# Dongle.net
KiCad netlist of a schematic drawn in EAGLE
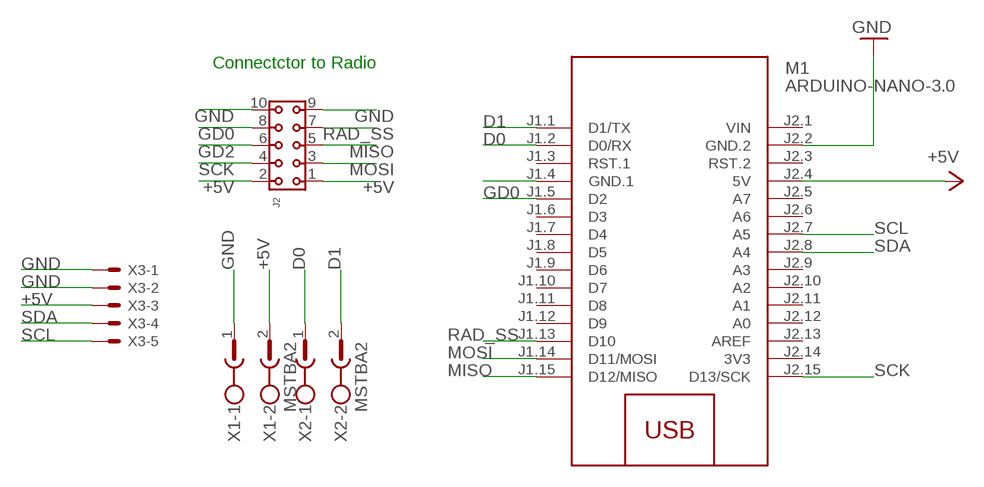
[diagram p0: schematic, sheet 1]

(export (version "E")
  (design (tool "Eeschema 10.0.6"))
  (components
    (comp (ref "J2")
      (value "6130XX21821_61301021821")
      (footprint "eagle-import:61301021821")
      (libsource (lib "eagle-import") (part "6130XX21821_61301021821"))
    )
    (comp (ref "M1")
      (value "ARDUINO-NANO-3.0")
      (footprint "eagle-import:ARDUINO-NANO-3.0")
      (libsource (lib "eagle-import") (part "ARDUINO-NANO-3.0"))
    )
    (comp (ref "X1")
      (value "MSTBA2")
      (footprint "eagle-import:MSTBA2")
      (fields (field (name "MF") "FARNELL") (field (name "MPN") "1757242"))
      (libsource (lib "eagle-import") (part "MSTBA2"))
    )
    (comp (ref "X2")
      (value "MSTBA2")
      (footprint "eagle-import:MSTBA2")
      (fields (field (name "MF") "FARNELL") (field (name "MPN") "1757242"))
      (libsource (lib "eagle-import") (part "MSTBA2"))
    )
    (comp (ref "X3")
      (value "KK-156-5")
      (footprint "eagle-import:KK-156-5")
      (fields (field (name "MF") "MOLEX"))
      (libsource (lib "eagle-import") (part "KK-156-5"))
    )
  )
  (nets
    (net (code "1") (name "+5V") (class "Default")
      (node (ref "J2") (pin "1") (pinfunction "1_1") (pintype "passive"))
      (node (ref "J2") (pin "2") (pinfunction "2_2") (pintype "passive"))
      (node (ref "M1") (pin "J2.4") (pinfunction "5V_J2.4") (pintype "power_in"))
      (node (ref "X1") (pin "2") (pinfunction "1_2") (pintype "passive"))
      (node (ref "X3") (pin "3") (pinfunction "S_3") (pintype "passive"))
    )
    (net (code "2") (name "/3V3") (class "Default")
      (node (ref "M1") (pin "J2.14") (pinfunction "3V3_J2.14") (pintype "power_in"))
    )
    (net (code "3") (name "/D0") (class "Default")
      (node (ref "M1") (pin "J1.2") (pinfunction "D0/RX_J1.2") (pintype "bidirectional"))
      (node (ref "X2") (pin "1") (pinfunction "1_1") (pintype "passive"))
    )
    (net (code "4") (name "/D1") (class "Default")
      (node (ref "M1") (pin "J1.1") (pinfunction "D1/TX_J1.1") (pintype "bidirectional"))
      (node (ref "X2") (pin "2") (pinfunction "1_2") (pintype "passive"))
    )
    (net (code "5") (name "/GD0") (class "Default")
      (node (ref "J2") (pin "8") (pinfunction "8_8") (pintype "passive"))
      (node (ref "M1") (pin "J1.5") (pinfunction "D2_J1.5") (pintype "bidirectional"))
    )
    (net (code "6") (name "/GD2") (class "Default")
      (node (ref "J2") (pin "6") (pinfunction "6_6") (pintype "passive"))
    )
    (net (code "7") (name "/MISO") (class "Default")
      (node (ref "J2") (pin "5") (pinfunction "5_5") (pintype "passive"))
      (node (ref "M1") (pin "J1.15") (pinfunction "D12/MISO_J1.15") (pintype "bidirectional"))
    )
    (net (code "8") (name "/MOSI") (class "Default")
      (node (ref "J2") (pin "3") (pinfunction "3_3") (pintype "passive"))
      (node (ref "M1") (pin "J1.14") (pinfunction "D11/MOSI_J1.14") (pintype "bidirectional"))
    )
    (net (code "9") (name "/RAD_SS") (class "Default")
      (node (ref "J2") (pin "7") (pinfunction "7_7") (pintype "passive"))
      (node (ref "M1") (pin "J1.13") (pinfunction "D10_J1.13") (pintype "bidirectional"))
    )
    (net (code "10") (name "/SCK") (class "Default")
      (node (ref "J2") (pin "4") (pinfunction "4_4") (pintype "passive"))
      (node (ref "M1") (pin "J2.15") (pinfunction "D13/SCK_J2.15") (pintype "bidirectional"))
    )
    (net (code "11") (name "/SCL") (class "Default")
      (node (ref "M1") (pin "J2.7") (pinfunction "A5_J2.7") (pintype "bidirectional"))
      (node (ref "X3") (pin "5") (pinfunction "S_5") (pintype "passive"))
    )
    (net (code "12") (name "/SDA") (class "Default")
      (node (ref "M1") (pin "J2.8") (pinfunction "A4_J2.8") (pintype "bidirectional"))
      (node (ref "X3") (pin "4") (pinfunction "S_4") (pintype "passive"))
    )
    (net (code "13") (name "/VIN") (class "Default")
      (node (ref "M1") (pin "J2.1") (pinfunction "VIN_J2.1") (pintype "power_in"))
    )
    (net (code "14") (name "GND") (class "Default")
      (node (ref "J2") (pin "10") (pinfunction "10_10") (pintype "passive"))
      (node (ref "J2") (pin "9") (pinfunction "9_9") (pintype "passive"))
      (node (ref "M1") (pin "J2.2") (pinfunction "GND.2_J2.2") (pintype "power_in"))
      (node (ref "X1") (pin "1") (pinfunction "1_1") (pintype "passive"))
      (node (ref "X3") (pin "1") (pinfunction "S_1") (pintype "passive"))
      (node (ref "X3") (pin "2") (pinfunction "S_2") (pintype "passive"))
    )
    (net (code "15") (name "unconnected-(M1-A0-PadJ2.12)") (class "Default")
      (node (ref "M1") (pin "J2.12") (pinfunction "A0_J2.12") (pintype "bidirectional"))
    )
    (net (code "16") (name "unconnected-(M1-A1-PadJ2.11)") (class "Default")
      (node (ref "M1") (pin "J2.11") (pinfunction "A1_J2.11") (pintype "bidirectional"))
    )
    (net (code "17") (name "unconnected-(M1-A2-PadJ2.10)") (class "Default")
      (node (ref "M1") (pin "J2.10") (pinfunction "A2_J2.10") (pintype "bidirectional"))
    )
    (net (code "18") (name "unconnected-(M1-A3-PadJ2.9)") (class "Default")
      (node (ref "M1") (pin "J2.9") (pinfunction "A3_J2.9") (pintype "bidirectional"))
    )
    (net (code "19") (name "unconnected-(M1-A6-PadJ2.6)") (class "Default")
      (node (ref "M1") (pin "J2.6") (pinfunction "A6_J2.6") (pintype "bidirectional"))
    )
    (net (code "20") (name "unconnected-(M1-A7-PadJ2.5)") (class "Default")
      (node (ref "M1") (pin "J2.5") (pinfunction "A7_J2.5") (pintype "bidirectional"))
    )
    (net (code "21") (name "unconnected-(M1-AREF-PadJ2.13)") (class "Default")
      (node (ref "M1") (pin "J2.13") (pinfunction "AREF_J2.13") (pintype "bidirectional"))
    )
    (net (code "22") (name "unconnected-(M1-D3-PadJ1.6)") (class "Default")
      (node (ref "M1") (pin "J1.6") (pinfunction "D3_J1.6") (pintype "bidirectional"))
    )
    (net (code "23") (name "unconnected-(M1-D4-PadJ1.7)") (class "Default")
      (node (ref "M1") (pin "J1.7") (pinfunction "D4_J1.7") (pintype "bidirectional"))
    )
    (net (code "24") (name "unconnected-(M1-D5-PadJ1.8)") (class "Default")
      (node (ref "M1") (pin "J1.8") (pinfunction "D5_J1.8") (pintype "bidirectional"))
    )
    (net (code "25") (name "unconnected-(M1-D6-PadJ1.9)") (class "Default")
      (node (ref "M1") (pin "J1.9") (pinfunction "D6_J1.9") (pintype "bidirectional"))
    )
    (net (code "26") (name "unconnected-(M1-D7-PadJ1.10)") (class "Default")
      (node (ref "M1") (pin "J1.10") (pinfunction "D7_J1.10") (pintype "bidirectional"))
    )
    (net (code "27") (name "unconnected-(M1-D8-PadJ1.11)") (class "Default")
      (node (ref "M1") (pin "J1.11") (pinfunction "D8_J1.11") (pintype "bidirectional"))
    )
    (net (code "28") (name "unconnected-(M1-D9-PadJ1.12)") (class "Default")
      (node (ref "M1") (pin "J1.12") (pinfunction "D9_J1.12") (pintype "bidirectional"))
    )
    (net (code "29") (name "unconnected-(M1-GND.1-PadJ1.4)") (class "Default")
      (node (ref "M1") (pin "J1.4") (pinfunction "GND.1_J1.4") (pintype "power_in"))
    )
    (net (code "30") (name "unconnected-(M1-RST.1-PadJ1.3)") (class "Default")
      (node (ref "M1") (pin "J1.3") (pinfunction "RST.1_J1.3") (pintype "bidirectional"))
    )
    (net (code "31") (name "unconnected-(M1-RST.2-PadJ2.3)") (class "Default")
      (node (ref "M1") (pin "J2.3") (pinfunction "RST.2_J2.3") (pintype "bidirectional"))
    )
  )
)
